# Schematic.net
KiCad netlist of a schematic drawn in EAGLE
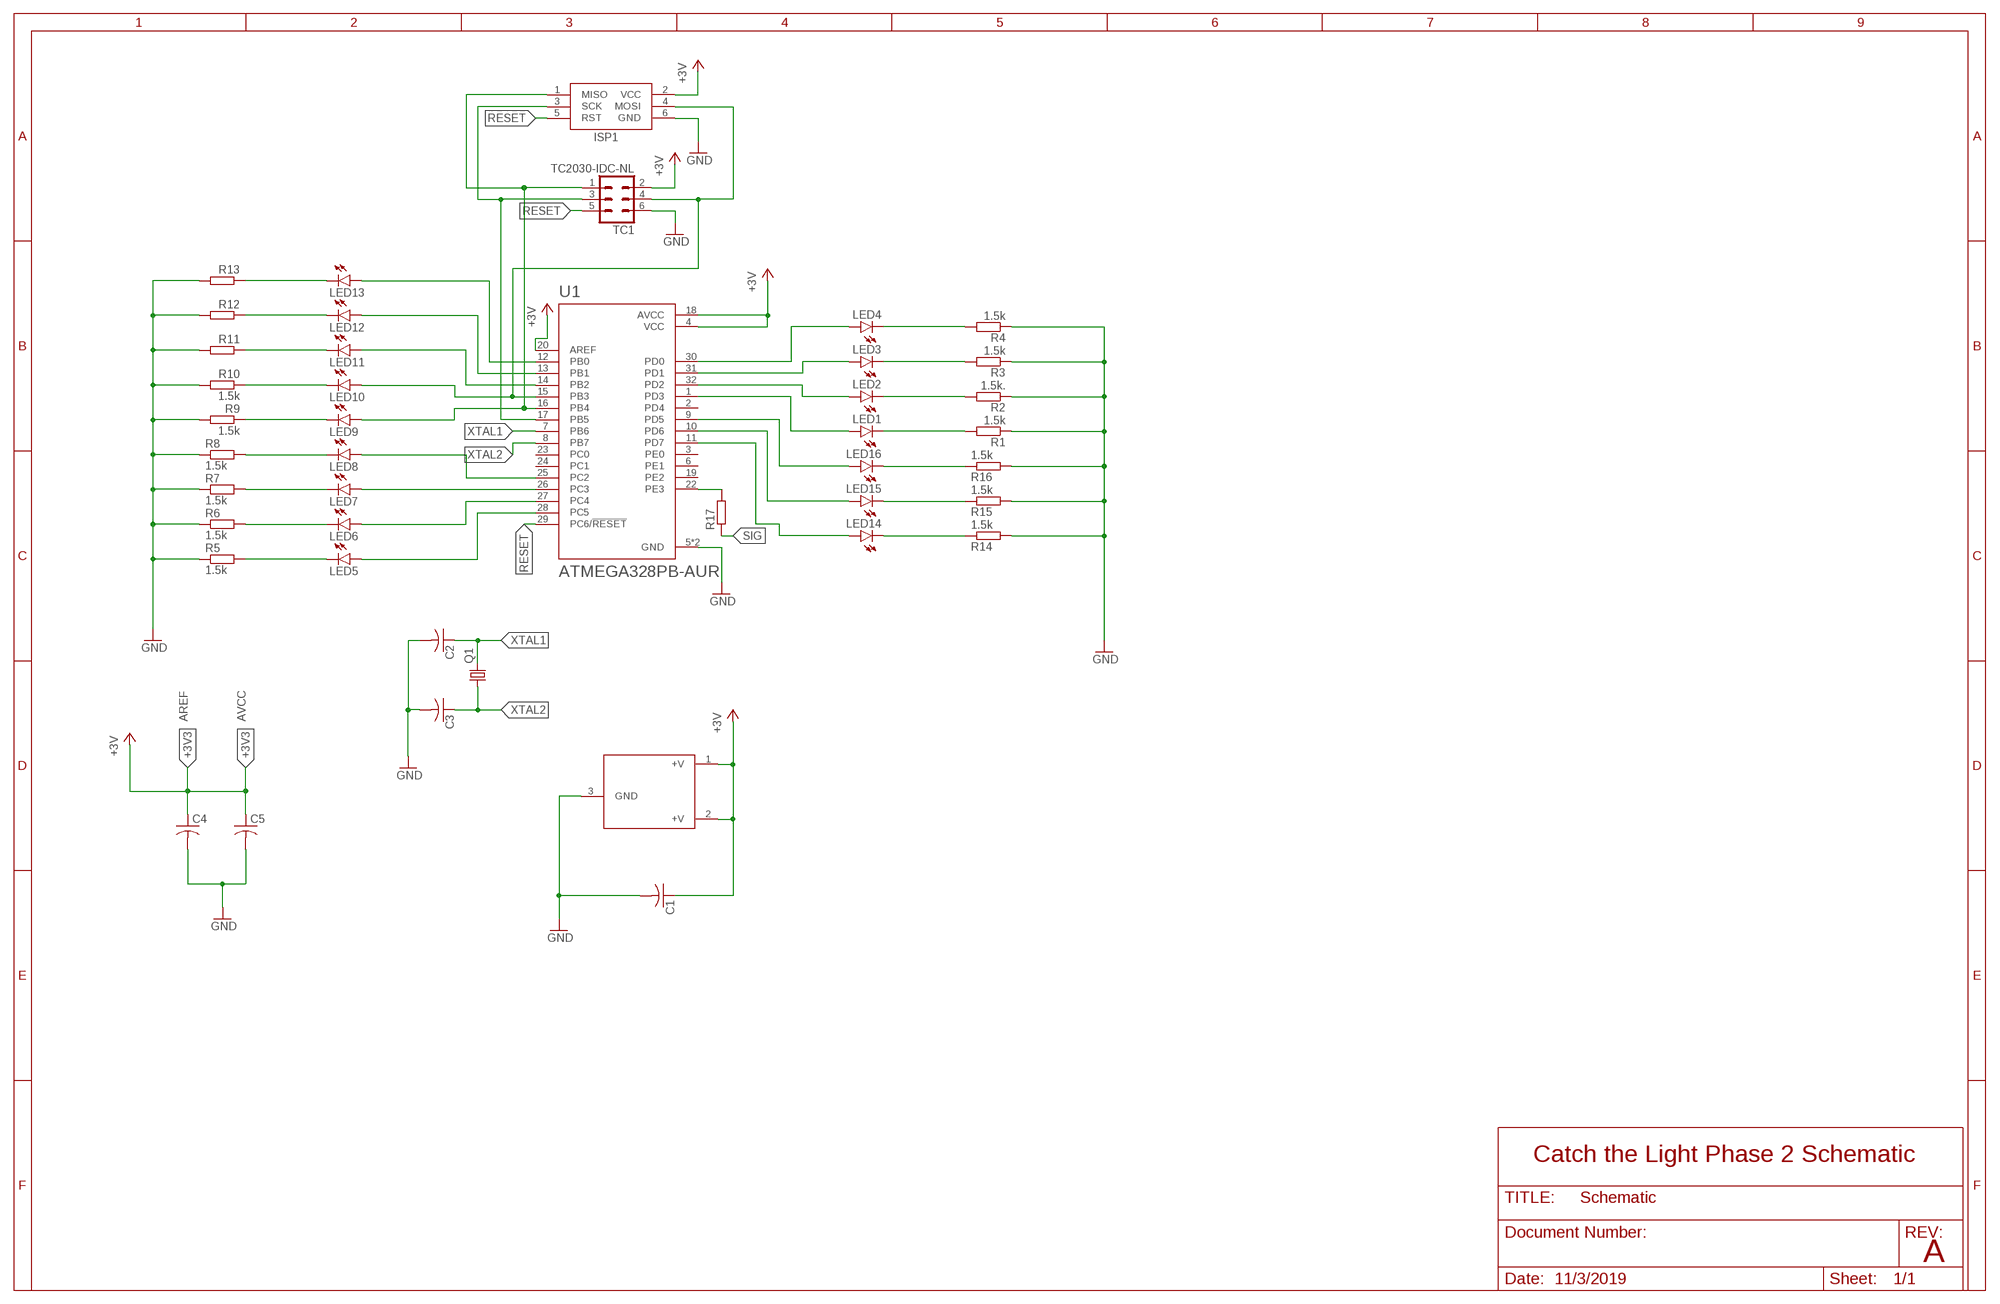
[diagram p0: schematic, sheet 1]

(export (version "E")
  (design (tool "Eeschema 10.0.6"))
  (components
    (comp (ref "BATT")
      (value "BC-2003SMD")
      (footprint "eagle-import:BC-2003")
      (libsource (lib "eagle-import") (part "BC-2003SMD"))
    )
    (comp (ref "C1")
      (value "C-USC0805")
      (footprint "eagle-import:C0805")
      (libsource (lib "eagle-import") (part "C-USC0805"))
    )
    (comp (ref "C2")
      (value "C-USC0805")
      (footprint "eagle-import:C0805")
      (libsource (lib "eagle-import") (part "C-USC0805"))
    )
    (comp (ref "C3")
      (value "C-USC0805")
      (footprint "eagle-import:C0805")
      (libsource (lib "eagle-import") (part "C-USC0805"))
    )
    (comp (ref "C4")
      (value "C-USC0805")
      (footprint "eagle-import:C0805")
      (libsource (lib "eagle-import") (part "C-USC0805"))
    )
    (comp (ref "C5")
      (value "C-USC0805")
      (footprint "eagle-import:C0805")
      (libsource (lib "eagle-import") (part "C-USC0805"))
    )
    (comp (ref "ISP1")
      (value "AVRISP-6")
      (footprint "eagle-import:AVRISP")
      (libsource (lib "eagle-import") (part "AVRISP-6"))
    )
    (comp (ref "LED1")
      (value "LEDCHIP-LED0805")
      (footprint "eagle-import:CHIP-LED0805")
      (libsource (lib "eagle-import") (part "LEDCHIP-LED0805"))
    )
    (comp (ref "LED2")
      (value "LEDCHIP-LED0805")
      (footprint "eagle-import:CHIP-LED0805")
      (libsource (lib "eagle-import") (part "LEDCHIP-LED0805"))
    )
    (comp (ref "LED3")
      (value "LEDCHIP-LED0805")
      (footprint "eagle-import:CHIP-LED0805")
      (libsource (lib "eagle-import") (part "LEDCHIP-LED0805"))
    )
    (comp (ref "LED4")
      (value "LEDCHIP-LED0805")
      (footprint "eagle-import:CHIP-LED0805")
      (libsource (lib "eagle-import") (part "LEDCHIP-LED0805"))
    )
    (comp (ref "LED5")
      (value "LEDCHIP-LED0805")
      (footprint "eagle-import:CHIP-LED0805")
      (libsource (lib "eagle-import") (part "LEDCHIP-LED0805"))
    )
    (comp (ref "LED6")
      (value "LEDCHIP-LED0805")
      (footprint "eagle-import:CHIP-LED0805")
      (libsource (lib "eagle-import") (part "LEDCHIP-LED0805"))
    )
    (comp (ref "LED7")
      (value "LEDCHIP-LED0805")
      (footprint "eagle-import:CHIP-LED0805")
      (libsource (lib "eagle-import") (part "LEDCHIP-LED0805"))
    )
    (comp (ref "LED8")
      (value "LEDCHIP-LED0805")
      (footprint "eagle-import:CHIP-LED0805")
      (libsource (lib "eagle-import") (part "LEDCHIP-LED0805"))
    )
    (comp (ref "LED9")
      (value "LEDCHIP-LED0805")
      (footprint "eagle-import:CHIP-LED0805")
      (libsource (lib "eagle-import") (part "LEDCHIP-LED0805"))
    )
    (comp (ref "LED10")
      (value "LEDCHIP-LED0805")
      (footprint "eagle-import:CHIP-LED0805")
      (libsource (lib "eagle-import") (part "LEDCHIP-LED0805"))
    )
    (comp (ref "LED11")
      (value "LEDCHIP-LED0805")
      (footprint "eagle-import:CHIP-LED0805")
      (libsource (lib "eagle-import") (part "LEDCHIP-LED0805"))
    )
    (comp (ref "LED12")
      (value "LEDCHIP-LED0805")
      (footprint "eagle-import:CHIP-LED0805")
      (libsource (lib "eagle-import") (part "LEDCHIP-LED0805"))
    )
    (comp (ref "LED13")
      (value "LEDCHIP-LED0805")
      (footprint "eagle-import:CHIP-LED0805")
      (libsource (lib "eagle-import") (part "LEDCHIP-LED0805"))
    )
    (comp (ref "LED14")
      (value "LEDCHIP-LED0805")
      (footprint "eagle-import:CHIP-LED0805")
      (libsource (lib "eagle-import") (part "LEDCHIP-LED0805"))
    )
    (comp (ref "LED15")
      (value "LEDCHIP-LED0805")
      (footprint "eagle-import:CHIP-LED0805")
      (libsource (lib "eagle-import") (part "LEDCHIP-LED0805"))
    )
    (comp (ref "LED16")
      (value "LEDCHIP-LED0805")
      (footprint "eagle-import:CHIP-LED0805")
      (libsource (lib "eagle-import") (part "LEDCHIP-LED0805"))
    )
    (comp (ref "Q1")
      (value "CRYSTALHC49UP")
      (footprint "eagle-import:HC49UP")
      (libsource (lib "eagle-import") (part "CRYSTALHC49UP"))
    )
    (comp (ref "R1")
      (value "1.5k")
      (footprint "eagle-import:R0805")
      (libsource (lib "eagle-import") (part "R-EU_R0805"))
    )
    (comp (ref "R2")
      (value "1.5k.")
      (footprint "eagle-import:R0805")
      (libsource (lib "eagle-import") (part "R-EU_R0805"))
    )
    (comp (ref "R3")
      (value "1.5k")
      (footprint "eagle-import:R0805")
      (libsource (lib "eagle-import") (part "R-EU_R0805"))
    )
    (comp (ref "R4")
      (value "1.5k")
      (footprint "eagle-import:R0805")
      (libsource (lib "eagle-import") (part "R-EU_R0805"))
    )
    (comp (ref "R5")
      (value "1.5k")
      (footprint "eagle-import:R0805")
      (libsource (lib "eagle-import") (part "R-EU_R0805"))
    )
    (comp (ref "R6")
      (value "1.5k")
      (footprint "eagle-import:R0805")
      (libsource (lib "eagle-import") (part "R-EU_R0805"))
    )
    (comp (ref "R7")
      (value "1.5k")
      (footprint "eagle-import:R0805")
      (libsource (lib "eagle-import") (part "R-EU_R0805"))
    )
    (comp (ref "R8")
      (value "1.5k")
      (footprint "eagle-import:R0805")
      (libsource (lib "eagle-import") (part "R-EU_R0805"))
    )
    (comp (ref "R9")
      (value "1.5k")
      (footprint "eagle-import:R0805")
      (libsource (lib "eagle-import") (part "R-EU_R0805"))
    )
    (comp (ref "R10")
      (value "1.5k")
      (footprint "eagle-import:R0805")
      (libsource (lib "eagle-import") (part "R-EU_R0805"))
    )
    (comp (ref "R11")
      (value "R-EU_R0805")
      (footprint "eagle-import:R0805")
      (libsource (lib "eagle-import") (part "R-EU_R0805"))
    )
    (comp (ref "R12")
      (value "R-EU_R0805")
      (footprint "eagle-import:R0805")
      (libsource (lib "eagle-import") (part "R-EU_R0805"))
    )
    (comp (ref "R13")
      (value "R-EU_R0805")
      (footprint "eagle-import:R0805")
      (libsource (lib "eagle-import") (part "R-EU_R0805"))
    )
    (comp (ref "R14")
      (value "1.5k")
      (footprint "eagle-import:R0805")
      (libsource (lib "eagle-import") (part "R-EU_R0805"))
    )
    (comp (ref "R15")
      (value "1.5k")
      (footprint "eagle-import:R0805")
      (libsource (lib "eagle-import") (part "R-EU_R0805"))
    )
    (comp (ref "R16")
      (value "1.5k")
      (footprint "eagle-import:R0805")
      (libsource (lib "eagle-import") (part "R-EU_R0805"))
    )
    (comp (ref "R17")
      (value "R-EU_R0805")
      (footprint "eagle-import:R0805")
      (libsource (lib "eagle-import") (part "R-EU_R0805"))
    )
    (comp (ref "TC1")
      (value "TC2030-IDC-NL")
      (footprint "eagle-import:TC2030-IDC-NL")
      (libsource (lib "eagle-import") (part "TC2030-IDC-NL"))
    )
    (comp (ref "U1")
      (value "ATMEGA328PB-AUR")
      (footprint "eagle-import:QFP80P900X900X120-32N")
      (fields (field (name "DIGI-KEY_PART_NUMBER") "ATMEGA328PB-AURCT-ND") (field (name "MF") "Microchip"))
      (libsource (lib "eagle-import") (part "ATMEGA328PB-AUR"))
    )
  )
  (nets
    (net (code "1") (name "+3V3") (class "Default")
      (node (ref "BATT") (pin "1") (pinfunction "+V_1") (pintype "bidirectional"))
      (node (ref "BATT") (pin "2") (pinfunction "+V_2") (pintype "bidirectional"))
      (node (ref "C1") (pin "1") (pinfunction "1_1") (pintype "passive"))
      (node (ref "C4") (pin "1") (pinfunction "1_1") (pintype "passive"))
      (node (ref "C5") (pin "1") (pinfunction "1_1") (pintype "passive"))
      (node (ref "ISP1") (pin "2") (pinfunction "VCC_2") (pintype "power_in"))
      (node (ref "TC1") (pin "2") (pinfunction "2_2") (pintype "passive"))
      (node (ref "U1") (pin "18") (pinfunction "AVCC_18") (pintype "power_in"))
      (node (ref "U1") (pin "20") (pinfunction "AREF_20") (pintype "input"))
      (node (ref "U1") (pin "4") (pinfunction "VCC_4") (pintype "power_in"))
    )
    (net (code "2") (name "GND") (class "Default")
      (node (ref "BATT") (pin "3") (pinfunction "GND_3") (pintype "bidirectional"))
      (node (ref "C1") (pin "2") (pinfunction "2_2") (pintype "passive"))
      (node (ref "C2") (pin "2") (pinfunction "2_2") (pintype "passive"))
      (node (ref "C3") (pin "2") (pinfunction "2_2") (pintype "passive"))
      (node (ref "C4") (pin "2") (pinfunction "2_2") (pintype "passive"))
      (node (ref "C5") (pin "2") (pinfunction "2_2") (pintype "passive"))
      (node (ref "ISP1") (pin "6") (pinfunction "GND_6") (pintype "power_in"))
      (node (ref "R1") (pin "1") (pinfunction "1_1") (pintype "passive"))
      (node (ref "R10") (pin "2") (pinfunction "2_2") (pintype "passive"))
      (node (ref "R11") (pin "2") (pinfunction "2_2") (pintype "passive"))
      (node (ref "R12") (pin "2") (pinfunction "2_2") (pintype "passive"))
      (node (ref "R13") (pin "2") (pinfunction "2_2") (pintype "passive"))
      (node (ref "R14") (pin "2") (pinfunction "2_2") (pintype "passive"))
      (node (ref "R15") (pin "2") (pinfunction "2_2") (pintype "passive"))
      (node (ref "R16") (pin "2") (pinfunction "2_2") (pintype "passive"))
      (node (ref "R2") (pin "1") (pinfunction "1_1") (pintype "passive"))
      (node (ref "R3") (pin "1") (pinfunction "1_1") (pintype "passive"))
      (node (ref "R4") (pin "1") (pinfunction "1_1") (pintype "passive"))
      (node (ref "R5") (pin "1") (pinfunction "1_1") (pintype "passive"))
      (node (ref "R6") (pin "1") (pinfunction "1_1") (pintype "passive"))
      (node (ref "R7") (pin "1") (pinfunction "1_1") (pintype "passive"))
      (node (ref "R8") (pin "1") (pinfunction "1_1") (pintype "passive"))
      (node (ref "R9") (pin "2") (pinfunction "2_2") (pintype "passive"))
      (node (ref "TC1") (pin "6") (pinfunction "6_6") (pintype "passive"))
      (node (ref "U1") (pin "21") (pinfunction "GND_21") (pintype "power_in"))
      (node (ref "U1") (pin "5") (pinfunction "GND_5") (pintype "power_in"))
    )
    (net (code "3") (name "Net-(ISP1-MISO)") (class "Default")
      (node (ref "ISP1") (pin "1") (pinfunction "MISO_1") (pintype "input"))
      (node (ref "LED9") (pin "A") (pinfunction "A_A") (pintype "passive"))
      (node (ref "TC1") (pin "1") (pinfunction "1_1") (pintype "passive"))
      (node (ref "U1") (pin "16") (pinfunction "PB4_16") (pintype "bidirectional"))
    )
    (net (code "4") (name "Net-(ISP1-MOSI)") (class "Default")
      (node (ref "ISP1") (pin "4") (pinfunction "MOSI_4") (pintype "output"))
      (node (ref "LED10") (pin "A") (pinfunction "A_A") (pintype "passive"))
      (node (ref "TC1") (pin "4") (pinfunction "4_4") (pintype "passive"))
      (node (ref "U1") (pin "15") (pinfunction "PB3_15") (pintype "bidirectional"))
    )
    (net (code "5") (name "Net-(ISP1-SCK)") (class "Default")
      (node (ref "ISP1") (pin "3") (pinfunction "SCK_3") (pintype "output"))
      (node (ref "TC1") (pin "3") (pinfunction "3_3") (pintype "passive"))
      (node (ref "U1") (pin "17") (pinfunction "PB5_17") (pintype "bidirectional"))
    )
    (net (code "6") (name "Net-(LED1-PadC)") (class "Default")
      (node (ref "LED1") (pin "C") (pinfunction "C_C") (pintype "passive"))
      (node (ref "R1") (pin "2") (pinfunction "2_2") (pintype "passive"))
    )
    (net (code "7") (name "Net-(LED2-PadC)") (class "Default")
      (node (ref "LED2") (pin "C") (pinfunction "C_C") (pintype "passive"))
      (node (ref "R2") (pin "2") (pinfunction "2_2") (pintype "passive"))
    )
    (net (code "8") (name "Net-(LED3-PadC)") (class "Default")
      (node (ref "LED3") (pin "C") (pinfunction "C_C") (pintype "passive"))
      (node (ref "R3") (pin "2") (pinfunction "2_2") (pintype "passive"))
    )
    (net (code "9") (name "Net-(LED4-PadC)") (class "Default")
      (node (ref "LED4") (pin "C") (pinfunction "C_C") (pintype "passive"))
      (node (ref "R4") (pin "2") (pinfunction "2_2") (pintype "passive"))
    )
    (net (code "10") (name "Net-(LED5-PadC)") (class "Default")
      (node (ref "LED5") (pin "C") (pinfunction "C_C") (pintype "passive"))
      (node (ref "R5") (pin "2") (pinfunction "2_2") (pintype "passive"))
    )
    (net (code "11") (name "Net-(LED6-PadC)") (class "Default")
      (node (ref "LED6") (pin "C") (pinfunction "C_C") (pintype "passive"))
      (node (ref "R6") (pin "2") (pinfunction "2_2") (pintype "passive"))
    )
    (net (code "12") (name "Net-(LED7-PadC)") (class "Default")
      (node (ref "LED7") (pin "C") (pinfunction "C_C") (pintype "passive"))
      (node (ref "R7") (pin "2") (pinfunction "2_2") (pintype "passive"))
    )
    (net (code "13") (name "Net-(LED8-PadC)") (class "Default")
      (node (ref "LED8") (pin "C") (pinfunction "C_C") (pintype "passive"))
      (node (ref "R8") (pin "2") (pinfunction "2_2") (pintype "passive"))
    )
    (net (code "14") (name "Net-(LED9-PadC)") (class "Default")
      (node (ref "LED9") (pin "C") (pinfunction "C_C") (pintype "passive"))
      (node (ref "R9") (pin "1") (pinfunction "1_1") (pintype "passive"))
    )
    (net (code "15") (name "Net-(LED10-PadC)") (class "Default")
      (node (ref "LED10") (pin "C") (pinfunction "C_C") (pintype "passive"))
      (node (ref "R10") (pin "1") (pinfunction "1_1") (pintype "passive"))
    )
    (net (code "16") (name "Net-(LED11-PadC)") (class "Default")
      (node (ref "LED11") (pin "C") (pinfunction "C_C") (pintype "passive"))
      (node (ref "R11") (pin "1") (pinfunction "1_1") (pintype "passive"))
    )
    (net (code "17") (name "Net-(LED12-PadC)") (class "Default")
      (node (ref "LED12") (pin "C") (pinfunction "C_C") (pintype "passive"))
      (node (ref "R12") (pin "1") (pinfunction "1_1") (pintype "passive"))
    )
    (net (code "18") (name "Net-(LED13-PadC)") (class "Default")
      (node (ref "LED13") (pin "C") (pinfunction "C_C") (pintype "passive"))
      (node (ref "R13") (pin "1") (pinfunction "1_1") (pintype "passive"))
    )
    (net (code "19") (name "Net-(LED14-PadC)") (class "Default")
      (node (ref "LED14") (pin "C") (pinfunction "C_C") (pintype "passive"))
      (node (ref "R14") (pin "1") (pinfunction "1_1") (pintype "passive"))
    )
    (net (code "20") (name "Net-(LED15-PadC)") (class "Default")
      (node (ref "LED15") (pin "C") (pinfunction "C_C") (pintype "passive"))
      (node (ref "R15") (pin "1") (pinfunction "1_1") (pintype "passive"))
    )
    (net (code "21") (name "Net-(LED16-PadC)") (class "Default")
      (node (ref "LED16") (pin "C") (pinfunction "C_C") (pintype "passive"))
      (node (ref "R16") (pin "1") (pinfunction "1_1") (pintype "passive"))
    )
    (net (code "22") (name "Net-(U1-PB0)") (class "Default")
      (node (ref "LED13") (pin "A") (pinfunction "A_A") (pintype "passive"))
      (node (ref "U1") (pin "12") (pinfunction "PB0_12") (pintype "bidirectional"))
    )
    (net (code "23") (name "Net-(U1-PB1)") (class "Default")
      (node (ref "LED12") (pin "A") (pinfunction "A_A") (pintype "passive"))
      (node (ref "U1") (pin "13") (pinfunction "PB1_13") (pintype "bidirectional"))
    )
    (net (code "24") (name "Net-(U1-PB2)") (class "Default")
      (node (ref "LED11") (pin "A") (pinfunction "A_A") (pintype "passive"))
      (node (ref "U1") (pin "14") (pinfunction "PB2_14") (pintype "bidirectional"))
    )
    (net (code "25") (name "Net-(U1-PC2)") (class "Default")
      (node (ref "LED8") (pin "A") (pinfunction "A_A") (pintype "passive"))
      (node (ref "U1") (pin "25") (pinfunction "PC2_25") (pintype "bidirectional"))
    )
    (net (code "26") (name "Net-(U1-PC3)") (class "Default")
      (node (ref "LED7") (pin "A") (pinfunction "A_A") (pintype "passive"))
      (node (ref "U1") (pin "26") (pinfunction "PC3_26") (pintype "bidirectional"))
    )
    (net (code "27") (name "Net-(U1-PC4)") (class "Default")
      (node (ref "LED6") (pin "A") (pinfunction "A_A") (pintype "passive"))
      (node (ref "U1") (pin "27") (pinfunction "PC4_27") (pintype "bidirectional"))
    )
    (net (code "28") (name "Net-(U1-PC5)") (class "Default")
      (node (ref "LED5") (pin "A") (pinfunction "A_A") (pintype "passive"))
      (node (ref "U1") (pin "28") (pinfunction "PC5_28") (pintype "bidirectional"))
    )
    (net (code "29") (name "Net-(U1-PD0)") (class "Default")
      (node (ref "LED4") (pin "A") (pinfunction "A_A") (pintype "passive"))
      (node (ref "U1") (pin "30") (pinfunction "PD0_30") (pintype "bidirectional"))
    )
    (net (code "30") (name "Net-(U1-PD1)") (class "Default")
      (node (ref "LED3") (pin "A") (pinfunction "A_A") (pintype "passive"))
      (node (ref "U1") (pin "31") (pinfunction "PD1_31") (pintype "bidirectional"))
    )
    (net (code "31") (name "Net-(U1-PD2)") (class "Default")
      (node (ref "LED2") (pin "A") (pinfunction "A_A") (pintype "passive"))
      (node (ref "U1") (pin "32") (pinfunction "PD2_32") (pintype "bidirectional"))
    )
    (net (code "32") (name "Net-(U1-PD3)") (class "Default")
      (node (ref "LED1") (pin "A") (pinfunction "A_A") (pintype "passive"))
      (node (ref "U1") (pin "1") (pinfunction "PD3_1") (pintype "bidirectional"))
    )
    (net (code "33") (name "Net-(U1-PD5)") (class "Default")
      (node (ref "LED16") (pin "A") (pinfunction "A_A") (pintype "passive"))
      (node (ref "U1") (pin "9") (pinfunction "PD5_9") (pintype "bidirectional"))
    )
    (net (code "34") (name "Net-(U1-PD6)") (class "Default")
      (node (ref "LED15") (pin "A") (pinfunction "A_A") (pintype "passive"))
      (node (ref "U1") (pin "10") (pinfunction "PD6_10") (pintype "bidirectional"))
    )
    (net (code "35") (name "Net-(U1-PD7)") (class "Default")
      (node (ref "LED14") (pin "A") (pinfunction "A_A") (pintype "passive"))
      (node (ref "U1") (pin "11") (pinfunction "PD7_11") (pintype "bidirectional"))
    )
    (net (code "36") (name "Net-(U1-PE3)") (class "Default")
      (node (ref "R17") (pin "2") (pinfunction "2_2") (pintype "passive"))
      (node (ref "U1") (pin "22") (pinfunction "PE3_22") (pintype "bidirectional"))
    )
    (net (code "37") (name "RESET") (class "Default")
      (node (ref "ISP1") (pin "5") (pinfunction "RST_5") (pintype "output"))
      (node (ref "TC1") (pin "5") (pinfunction "5_5") (pintype "passive"))
      (node (ref "U1") (pin "29") (pinfunction "PC6/~{RESET}_29") (pintype "bidirectional"))
    )
    (net (code "38") (name "SIG") (class "Default")
      (node (ref "R17") (pin "1") (pinfunction "1_1") (pintype "passive"))
    )
    (net (code "39") (name "XTAL1") (class "Default")
      (node (ref "C2") (pin "1") (pinfunction "1_1") (pintype "passive"))
      (node (ref "Q1") (pin "2") (pinfunction "2_2") (pintype "passive"))
      (node (ref "U1") (pin "7") (pinfunction "PB6_7") (pintype "bidirectional"))
    )
    (net (code "40") (name "XTAL2") (class "Default")
      (node (ref "C3") (pin "1") (pinfunction "1_1") (pintype "passive"))
      (node (ref "Q1") (pin "1") (pinfunction "1_1") (pintype "passive"))
      (node (ref "U1") (pin "8") (pinfunction "PB7_8") (pintype "bidirectional"))
    )
    (net (code "41") (name "unconnected-(U1-PC0-Pad23)") (class "Default")
      (node (ref "U1") (pin "23") (pinfunction "PC0_23") (pintype "bidirectional"))
    )
    (net (code "42") (name "unconnected-(U1-PC1-Pad24)") (class "Default")
      (node (ref "U1") (pin "24") (pinfunction "PC1_24") (pintype "bidirectional"))
    )
    (net (code "43") (name "unconnected-(U1-PD4-Pad2)") (class "Default")
      (node (ref "U1") (pin "2") (pinfunction "PD4_2") (pintype "bidirectional"))
    )
    (net (code "44") (name "unconnected-(U1-PE0-Pad3)") (class "Default")
      (node (ref "U1") (pin "3") (pinfunction "PE0_3") (pintype "bidirectional"))
    )
    (net (code "45") (name "unconnected-(U1-PE1-Pad6)") (class "Default")
      (node (ref "U1") (pin "6") (pinfunction "PE1_6") (pintype "bidirectional"))
    )
    (net (code "46") (name "unconnected-(U1-PE2-Pad19)") (class "Default")
      (node (ref "U1") (pin "19") (pinfunction "PE2_19") (pintype "bidirectional"))
    )
  )
)
